# SoC.net
KiCad netlist of a schematic drawn in Altium Designer
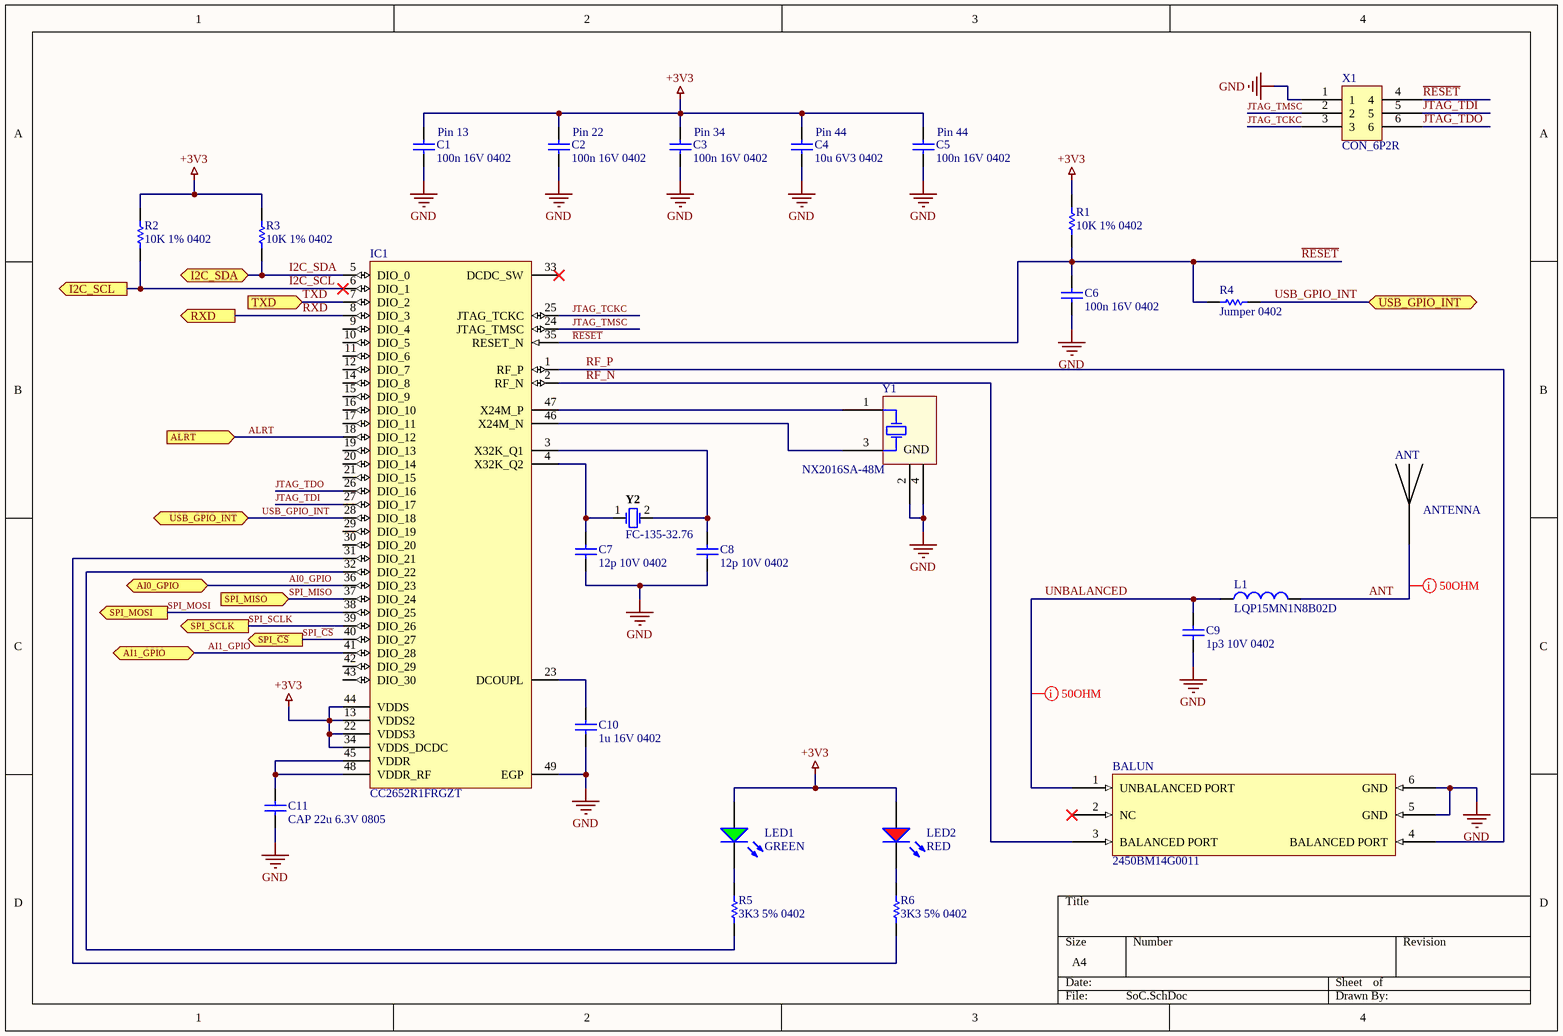
[diagram p0: SoC.SchDoc]

(export (version "E")
  (design (tool "Eeschema 10.0.6"))
  (components
    (comp (ref "ANT")
      (value "ANTENNA")
      (footprint "MOLEX_47948-0001")
      (libsource (lib "bleimuv6_intlib") (part "ANTENNA"))
    )
    (comp (ref "BALUN")
      (value "2450BM14G0011")
      (footprint "SON50P80X70-6L")
      (libsource (lib "bleimuv6_intlib") (part "2450BM14G0011"))
    )
    (comp (ref "C1")
      (value "100n 16V 0402")
      (footprint "CAPC0402(1005)60_L")
      (description "CAP 100nF 16V ±10% 0402 (1005 Metric) Thickness 0.6mm SMD")
      (fields (field (name "TOLERANCE") "Â±10%"))
      (libsource (lib "Altium Content Vault") (part "CAP"))
    )
    (comp (ref "C2")
      (value "100n 16V 0402")
      (footprint "CAPC0402(1005)60_L")
      (description "CAP 100nF 16V ±10% 0402 (1005 Metric) Thickness 0.6mm SMD")
      (fields (field (name "TOLERANCE") "Â±10%"))
      (libsource (lib "Altium Content Vault") (part "CAP"))
    )
    (comp (ref "C3")
      (value "100n 16V 0402")
      (footprint "CAPC0402(1005)60_L")
      (description "CAP 100nF 16V ±10% 0402 (1005 Metric) Thickness 0.6mm SMD")
      (fields (field (name "TOLERANCE") "Â±10%"))
      (libsource (lib "Altium Content Vault") (part "CAP"))
    )
    (comp (ref "C4")
      (value "10u 6V3 0402")
      (footprint "CAPC0402(1005)60_L")
      (description "CAP 10uF 6.3V ±20% 0402 (1005 Metric) Thickness 0.6mm SMD")
      (fields (field (name "TOLERANCE") "Â±20%"))
      (libsource (lib "Altium Content Vault") (part "CAP"))
    )
    (comp (ref "C5")
      (value "100n 16V 0402")
      (footprint "CAPC0402(1005)60_L")
      (description "CAP 100nF 16V ±10% 0402 (1005 Metric) Thickness 0.6mm SMD")
      (fields (field (name "TOLERANCE") "Â±10%"))
      (libsource (lib "Altium Content Vault") (part "CAP"))
    )
    (comp (ref "C6")
      (value "100n 16V 0402")
      (footprint "CAPC0402(1005)60_L")
      (description "CAP 100nF 16V ±10% 0402 (1005 Metric) Thickness 0.6mm SMD")
      (fields (field (name "TOLERANCE") "Â±10%"))
      (libsource (lib "Altium Content Vault") (part "CAP"))
    )
    (comp (ref "C7")
      (value "12p 10V 0402")
      (footprint "CAPC0402(1005)60_L")
      (description "CAP 12pF 10V ±1% 0402 (1005 Metric) Thickness 0.6mm SMD")
      (fields (field (name "TOLERANCE") "Â±1%"))
      (libsource (lib "Altium Content Vault") (part "CAP"))
    )
    (comp (ref "C8")
      (value "12p 10V 0402")
      (footprint "CAPC0402(1005)60_L")
      (description "CAP 12pF 10V ±1% 0402 (1005 Metric) Thickness 0.6mm SMD")
      (fields (field (name "TOLERANCE") "Â±1%"))
      (libsource (lib "Altium Content Vault") (part "CAP"))
    )
    (comp (ref "C9")
      (value "1p3 10V 0402")
      (footprint "CAPC0402(1005)60_M")
      (description "CAP 1.3pF 10V ±0.25pF 0402 (1005 Metric) Thickness 0.6mm SMD")
      (fields (field (name "TOLERANCE") "Â±0.25pF"))
      (libsource (lib "Altium Content Vault") (part "CAP"))
    )
    (comp (ref "C10")
      (value "1u 16V 0402")
      (footprint "CAPC0402(1005)60_N")
      (description "CAP 1uF 16V ±10% 0402 (1005 Metric) Thickness 0.6mm SMD")
      (fields (field (name "TOLERANCE") "Â±10%"))
      (libsource (lib "Altium Content Vault") (part "CAP"))
    )
    (comp (ref "C11")
      (value "CAP 22u 6.3V 0805")
      (footprint "CAPC0805(2012)145_L")
      (description "CAP 22uF 6.3V ±10% 0805 (2012 Metric) Thickness 1.45mm SMD")
      (fields (field (name "TOLERANCE") "Â±10%"))
      (libsource (lib "Altium Content Vault") (part "CAP"))
    )
    (comp (ref "IC1")
      (value "CC2652R1FRGZT")
      (footprint "RGZ0048A_V")
      (fields (field (name "MANUFACTURER") "Texas Instruments"))
      (libsource (lib "Altium Content Vault") (part "TI-CC2650-VFQFN-48"))
    )
    (comp (ref "L1")
      (value "LQP15MN1N8B02D")
      (footprint "INDC1005X45X25ML10T10")
      (description "Chip Inductor, 1.8 nH, +/- 0.1 nH, 280 mA, -40 to 85 degC, 0402 (1005 Metric), RoHS, Tape and Reel")
      (fields (field (name "MANUFACTURER") "Murata"))
      (libsource (lib "Altium Content Vault") (part "IND-2"))
    )
    (comp (ref "LED1")
      (value "GREEN")
      (footprint "LED_0402")
      (description "Generic 0402 LED")
      (libsource (lib "bleimuv6_schlib") (part "LED"))
    )
    (comp (ref "LED2")
      (value "RED")
      (footprint "LED_0402")
      (description "Generic 0402 LED")
      (libsource (lib "bleimuv6_schlib") (part "LED"))
    )
    (comp (ref "R1")
      (value "10K 1% 0402")
      (footprint "RESC0402(1005)_L")
      (description "10K 0.063W 1% 0402 (1005 Metric)  SMD")
      (fields (field (name "TOLERANCE") "1 %") (field (name "POWER") "0.063 W"))
      (libsource (lib "Altium Content Vault") (part "RES"))
    )
    (comp (ref "R2")
      (value "10K 1% 0402")
      (footprint "RESC0402(1005)_L")
      (description "10K 0.063W 1% 0402 (1005 Metric)  SMD")
      (fields (field (name "TOLERANCE") "1 %") (field (name "POWER") "0.063 W"))
      (libsource (lib "Altium Content Vault") (part "RES"))
    )
    (comp (ref "R3")
      (value "10K 1% 0402")
      (footprint "RESC0402(1005)_L")
      (description "10K 0.063W 1% 0402 (1005 Metric)  SMD")
      (fields (field (name "TOLERANCE") "1 %") (field (name "POWER") "0.063 W"))
      (libsource (lib "Altium Content Vault") (part "RES"))
    )
    (comp (ref "R4")
      (value "Jumper 0402")
      (footprint "RESC0402(1005)_L")
      (description "Jumper 0402 (1005 Metric)")
      (fields (field (name "TOLERANCE") "None"))
      (libsource (lib "Altium Content Vault") (part "RES"))
    )
    (comp (ref "R5")
      (value "3K3 5% 0402")
      (footprint "RESC0402(1005)_L")
      (description "3K3 0.063W 5% 0402 (1005 Metric)  SMD")
      (fields (field (name "POWER") "0.063 W") (field (name "TOLERANCE") "5 %"))
      (libsource (lib "Altium Content Vault") (part "RES"))
    )
    (comp (ref "R6")
      (value "3K3 5% 0402")
      (footprint "RESC0402(1005)_L")
      (description "3K3 0.063W 5% 0402 (1005 Metric)  SMD")
      (fields (field (name "POWER") "0.063 W") (field (name "TOLERANCE") "5 %"))
      (libsource (lib "Altium Content Vault") (part "RES"))
    )
    (comp (ref "X1")
      (value "CON_6P2R")
      (footprint "JTAG_Con")
      (libsource (lib "bleimuv6_schlib") (part "CON_6P2R"))
    )
    (comp (ref "Y1")
      (value "NX2016SA-48M")
      (footprint "Crystal_2016")
      (libsource (lib "bleimuv6_intlib") (part "NX2016SA"))
    )
    (comp (ref "Y2")
      (value "FC-135-32.76")
      (footprint "EPSON-FC-135_V")
      (description "Crystal Unit, 32 to 77.5 KHz, 0.5 uW, -40 to 85 degC, 2-Pin SMD, RoHS")
      (fields (field (name "MANUFACTURER") "Epson"))
      (libsource (lib "Altium Content Vault") (part "XTAL-1-2-2"))
    )
  )
  (nets
    (net (code "1") (name "+3V3") (class "Default")
      (node (ref "C1") (pin "2") (pinfunction "2_2") (pintype "passive"))
      (node (ref "C2") (pin "2") (pinfunction "2_2") (pintype "passive"))
      (node (ref "C3") (pin "2") (pinfunction "2_2") (pintype "passive"))
      (node (ref "C4") (pin "2") (pinfunction "2_2") (pintype "passive"))
      (node (ref "C5") (pin "2") (pinfunction "2_2") (pintype "passive"))
      (node (ref "IC1") (pin "13") (pinfunction "VDDS2_13") (pintype "power_in"))
      (node (ref "IC1") (pin "22") (pinfunction "VDDS3_22") (pintype "power_in"))
      (node (ref "IC1") (pin "34") (pinfunction "VDDS_DCDC_34") (pintype "power_in"))
      (node (ref "IC1") (pin "44") (pinfunction "VDDS_44") (pintype "power_in"))
      (node (ref "LED1") (pin "ANODE") (pinfunction "ANODE_ANODE") (pintype "passive"))
      (node (ref "LED2") (pin "ANODE") (pinfunction "ANODE_ANODE") (pintype "passive"))
      (node (ref "R1") (pin "2") (pinfunction "2_2") (pintype "passive"))
      (node (ref "R2") (pin "2") (pinfunction "2_2") (pintype "passive"))
      (node (ref "R3") (pin "2") (pinfunction "2_2") (pintype "passive"))
    )
    (net (code "2") (name "/AI0_GPIO") (class "Default")
      (node (ref "IC1") (pin "36") (pinfunction "DIO_23_36") (pintype "bidirectional"))
    )
    (net (code "3") (name "/AI1_GPIO") (class "Default")
      (node (ref "IC1") (pin "41") (pinfunction "DIO_28_41") (pintype "bidirectional"))
    )
    (net (code "4") (name "/ALRT") (class "Default")
      (node (ref "IC1") (pin "18") (pinfunction "DIO_12_18") (pintype "bidirectional"))
    )
    (net (code "5") (name "/ANT") (class "Default")
      (node (ref "ANT") (pin "ANTENNA") (pinfunction "23_ANTENNA") (pintype "passive"))
      (node (ref "L1") (pin "2") (pinfunction "2_2") (pintype "passive"))
    )
    (net (code "6") (name "/I2C_SCL") (class "Default")
      (node (ref "IC1") (pin "6") (pinfunction "DIO_1_6") (pintype "bidirectional"))
      (node (ref "R2") (pin "1") (pinfunction "1_1") (pintype "passive"))
    )
    (net (code "7") (name "/I2C_SDA") (class "Default")
      (node (ref "IC1") (pin "5") (pinfunction "DIO_0_5") (pintype "bidirectional"))
      (node (ref "R3") (pin "1") (pinfunction "1_1") (pintype "passive"))
    )
    (net (code "8") (name "/JTAG_TCKC") (class "Default")
      (node (ref "IC1") (pin "25") (pinfunction "JTAG_TCKC_25") (pintype "bidirectional"))
      (node (ref "X1") (pin "3") (pinfunction "3_3") (pintype "passive"))
    )
    (net (code "9") (name "/JTAG_TDI") (class "Default")
      (node (ref "IC1") (pin "27") (pinfunction "DIO_17_27") (pintype "bidirectional"))
      (node (ref "X1") (pin "5") (pinfunction "5_5") (pintype "passive"))
    )
    (net (code "10") (name "/JTAG_TDO") (class "Default")
      (node (ref "IC1") (pin "26") (pinfunction "DIO_16_26") (pintype "bidirectional"))
      (node (ref "X1") (pin "6") (pinfunction "6_6") (pintype "passive"))
    )
    (net (code "11") (name "/JTAG_TMSC") (class "Default")
      (node (ref "IC1") (pin "24") (pinfunction "JTAG_TMSC_24") (pintype "bidirectional"))
      (node (ref "X1") (pin "2") (pinfunction "2_2") (pintype "passive"))
    )
    (net (code "12") (name "/RF_N") (class "Default")
      (node (ref "BALUN") (pin "3") (pinfunction "BALANCED_PORT_3") (pintype "input"))
      (node (ref "IC1") (pin "2") (pinfunction "RF_N_2") (pintype "bidirectional"))
    )
    (net (code "13") (name "/RF_P") (class "Default")
      (node (ref "BALUN") (pin "4") (pinfunction "BALANCED_PORT_4") (pintype "input"))
      (node (ref "IC1") (pin "1") (pinfunction "RF_P_1") (pintype "bidirectional"))
    )
    (net (code "14") (name "/RXD") (class "Default")
      (node (ref "IC1") (pin "8") (pinfunction "DIO_3_8") (pintype "bidirectional"))
    )
    (net (code "15") (name "/SPI_MISO") (class "Default")
      (node (ref "IC1") (pin "37") (pinfunction "DIO_24_37") (pintype "bidirectional"))
    )
    (net (code "16") (name "/SPI_MOSI") (class "Default")
      (node (ref "IC1") (pin "38") (pinfunction "DIO_25_38") (pintype "bidirectional"))
    )
    (net (code "17") (name "/SPI_SCLK") (class "Default")
      (node (ref "IC1") (pin "39") (pinfunction "DIO_26_39") (pintype "bidirectional"))
    )
    (net (code "18") (name "/SPI_~{CS}") (class "Default")
      (node (ref "IC1") (pin "40") (pinfunction "DIO_27_40") (pintype "bidirectional"))
    )
    (net (code "19") (name "/TXD") (class "Default")
      (node (ref "IC1") (pin "7") (pinfunction "DIO_2_7") (pintype "bidirectional"))
    )
    (net (code "20") (name "/UNBALANCED") (class "Default")
      (node (ref "BALUN") (pin "1") (pinfunction "UNBALANCED_PORT_1") (pintype "input"))
      (node (ref "C9") (pin "2") (pinfunction "2_2") (pintype "passive"))
      (node (ref "L1") (pin "1") (pinfunction "1_1") (pintype "passive"))
    )
    (net (code "21") (name "/USB_GPIO_INT") (class "Default")
      (node (ref "IC1") (pin "28") (pinfunction "DIO_18_28") (pintype "bidirectional"))
      (node (ref "R4") (pin "2") (pinfunction "2_2") (pintype "passive"))
    )
    (net (code "22") (name "/~{RESET}") (class "Default")
      (node (ref "C6") (pin "2") (pinfunction "2_2") (pintype "passive"))
      (node (ref "IC1") (pin "35") (pinfunction "RESET_N_35") (pintype "input"))
      (node (ref "R1") (pin "1") (pinfunction "1_1") (pintype "passive"))
      (node (ref "R4") (pin "1") (pinfunction "1_1") (pintype "passive"))
      (node (ref "X1") (pin "4") (pinfunction "4_4") (pintype "passive"))
    )
    (net (code "23") (name "GND") (class "Default")
      (node (ref "BALUN") (pin "5") (pinfunction "GND_5") (pintype "input"))
      (node (ref "BALUN") (pin "6") (pinfunction "GND_6") (pintype "input"))
      (node (ref "C1") (pin "1") (pinfunction "1_1") (pintype "passive"))
      (node (ref "C10") (pin "1") (pinfunction "1_1") (pintype "passive"))
      (node (ref "C11") (pin "1") (pinfunction "1_1") (pintype "passive"))
      (node (ref "C2") (pin "1") (pinfunction "1_1") (pintype "passive"))
      (node (ref "C3") (pin "1") (pinfunction "1_1") (pintype "passive"))
      (node (ref "C4") (pin "1") (pinfunction "1_1") (pintype "passive"))
      (node (ref "C5") (pin "1") (pinfunction "1_1") (pintype "passive"))
      (node (ref "C6") (pin "1") (pinfunction "1_1") (pintype "passive"))
      (node (ref "C7") (pin "1") (pinfunction "1_1") (pintype "passive"))
      (node (ref "C8") (pin "1") (pinfunction "1_1") (pintype "passive"))
      (node (ref "C9") (pin "1") (pinfunction "1_1") (pintype "passive"))
      (node (ref "IC1") (pin "49") (pinfunction "EGP_49") (pintype "power_in"))
      (node (ref "X1") (pin "1") (pinfunction "1_1") (pintype "passive"))
      (node (ref "Y1") (pin "2") (pinfunction "GND_2") (pintype "passive"))
      (node (ref "Y1") (pin "4") (pinfunction "GND_4") (pintype "passive"))
    )
    (net (code "24") (name "Net-(IC1-DCOUPL)") (class "Default")
      (node (ref "C10") (pin "2") (pinfunction "2_2") (pintype "passive"))
      (node (ref "IC1") (pin "23") (pinfunction "DCOUPL_23") (pintype "passive"))
    )
    (net (code "25") (name "Net-(IC1-DIO_21)") (class "Default")
      (node (ref "IC1") (pin "31") (pinfunction "DIO_21_31") (pintype "bidirectional"))
      (node (ref "R6") (pin "1") (pinfunction "1_1") (pintype "passive"))
    )
    (net (code "26") (name "Net-(IC1-DIO_22)") (class "Default")
      (node (ref "IC1") (pin "32") (pinfunction "DIO_22_32") (pintype "bidirectional"))
      (node (ref "R5") (pin "1") (pinfunction "1_1") (pintype "passive"))
    )
    (net (code "27") (name "Net-(IC1-VDDR)") (class "Default")
      (node (ref "C11") (pin "2") (pinfunction "2_2") (pintype "passive"))
      (node (ref "IC1") (pin "45") (pinfunction "VDDR_45") (pintype "power_in"))
      (node (ref "IC1") (pin "48") (pinfunction "VDDR_RF_48") (pintype "power_in"))
    )
    (net (code "28") (name "Net-(IC1-X24M_N)") (class "Default")
      (node (ref "IC1") (pin "46") (pinfunction "X24M_N_46") (pintype "passive"))
      (node (ref "Y1") (pin "3") (pinfunction "X2_3") (pintype "passive"))
    )
    (net (code "29") (name "Net-(IC1-X24M_P)") (class "Default")
      (node (ref "IC1") (pin "47") (pinfunction "X24M_P_47") (pintype "passive"))
      (node (ref "Y1") (pin "1") (pinfunction "X1_1") (pintype "passive"))
    )
    (net (code "30") (name "Net-(IC1-X32K_Q1)") (class "Default")
      (node (ref "C8") (pin "2") (pinfunction "2_2") (pintype "passive"))
      (node (ref "IC1") (pin "3") (pinfunction "X32K_Q1_3") (pintype "passive"))
      (node (ref "Y2") (pin "2") (pinfunction "2_2") (pintype "passive"))
    )
    (net (code "31") (name "Net-(IC1-X32K_Q2)") (class "Default")
      (node (ref "C7") (pin "2") (pinfunction "2_2") (pintype "passive"))
      (node (ref "IC1") (pin "4") (pinfunction "X32K_Q2_4") (pintype "passive"))
      (node (ref "Y2") (pin "1") (pinfunction "1_1") (pintype "passive"))
    )
    (net (code "32") (name "Net-(LED1-PadCATHODE)") (class "Default")
      (node (ref "LED1") (pin "CATHODE") (pinfunction "CATHODE_CATHODE") (pintype "passive"))
      (node (ref "R5") (pin "2") (pinfunction "2_2") (pintype "passive"))
    )
    (net (code "33") (name "Net-(LED2-PadCATHODE)") (class "Default")
      (node (ref "LED2") (pin "CATHODE") (pinfunction "CATHODE_CATHODE") (pintype "passive"))
      (node (ref "R6") (pin "2") (pinfunction "2_2") (pintype "passive"))
    )
    (net (code "34") (name "unconnected-(BALUN-NC-Pad2)") (class "Default")
      (node (ref "BALUN") (pin "2") (pinfunction "NC_2") (pintype "input+no_connect"))
    )
    (net (code "35") (name "unconnected-(IC1-DCDC_SW-Pad33)") (class "Default")
      (node (ref "IC1") (pin "33") (pinfunction "DCDC_SW_33") (pintype "power_in+no_connect"))
    )
    (net (code "36") (name "unconnected-(IC1-DIO_4-Pad9)") (class "Default")
      (node (ref "IC1") (pin "9") (pinfunction "DIO_4_9") (pintype "bidirectional"))
    )
    (net (code "37") (name "unconnected-(IC1-DIO_5-Pad10)") (class "Default")
      (node (ref "IC1") (pin "10") (pinfunction "DIO_5_10") (pintype "bidirectional"))
    )
    (net (code "38") (name "unconnected-(IC1-DIO_6-Pad11)") (class "Default")
      (node (ref "IC1") (pin "11") (pinfunction "DIO_6_11") (pintype "bidirectional"))
    )
    (net (code "39") (name "unconnected-(IC1-DIO_7-Pad12)") (class "Default")
      (node (ref "IC1") (pin "12") (pinfunction "DIO_7_12") (pintype "bidirectional"))
    )
    (net (code "40") (name "unconnected-(IC1-DIO_8-Pad14)") (class "Default")
      (node (ref "IC1") (pin "14") (pinfunction "DIO_8_14") (pintype "bidirectional"))
    )
    (net (code "41") (name "unconnected-(IC1-DIO_9-Pad15)") (class "Default")
      (node (ref "IC1") (pin "15") (pinfunction "DIO_9_15") (pintype "bidirectional"))
    )
    (net (code "42") (name "unconnected-(IC1-DIO_10-Pad16)") (class "Default")
      (node (ref "IC1") (pin "16") (pinfunction "DIO_10_16") (pintype "bidirectional"))
    )
    (net (code "43") (name "unconnected-(IC1-DIO_11-Pad17)") (class "Default")
      (node (ref "IC1") (pin "17") (pinfunction "DIO_11_17") (pintype "bidirectional"))
    )
    (net (code "44") (name "unconnected-(IC1-DIO_13-Pad19)") (class "Default")
      (node (ref "IC1") (pin "19") (pinfunction "DIO_13_19") (pintype "bidirectional"))
    )
    (net (code "45") (name "unconnected-(IC1-DIO_14-Pad20)") (class "Default")
      (node (ref "IC1") (pin "20") (pinfunction "DIO_14_20") (pintype "bidirectional"))
    )
    (net (code "46") (name "unconnected-(IC1-DIO_15-Pad21)") (class "Default")
      (node (ref "IC1") (pin "21") (pinfunction "DIO_15_21") (pintype "bidirectional"))
    )
    (net (code "47") (name "unconnected-(IC1-DIO_19-Pad29)") (class "Default")
      (node (ref "IC1") (pin "29") (pinfunction "DIO_19_29") (pintype "bidirectional"))
    )
    (net (code "48") (name "unconnected-(IC1-DIO_20-Pad30)") (class "Default")
      (node (ref "IC1") (pin "30") (pinfunction "DIO_20_30") (pintype "bidirectional"))
    )
    (net (code "49") (name "unconnected-(IC1-DIO_29-Pad42)") (class "Default")
      (node (ref "IC1") (pin "42") (pinfunction "DIO_29_42") (pintype "bidirectional"))
    )
    (net (code "50") (name "unconnected-(IC1-DIO_30-Pad43)") (class "Default")
      (node (ref "IC1") (pin "43") (pinfunction "DIO_30_43") (pintype "bidirectional"))
    )
  )
)
